# CAN_3V3.net
KiCad netlist of a schematic drawn in Altium Designer
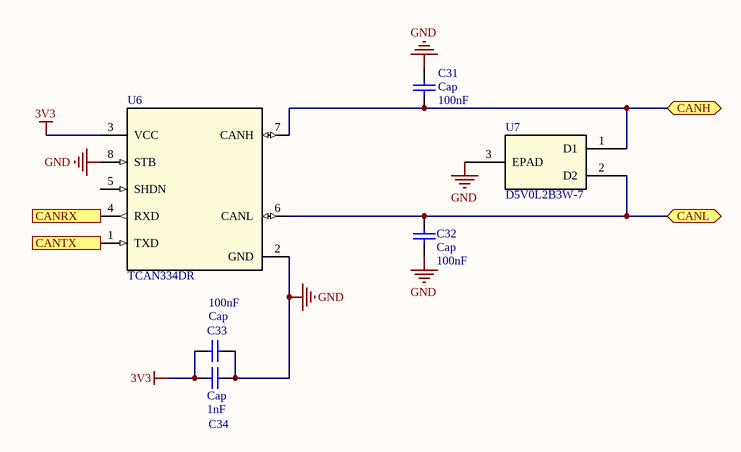
[diagram p0: CAN 3V3.SchDoc]

(export (version "E")
  (design (tool "Eeschema 10.0.6"))
  (components
    (comp (ref "C31")
      (value "Cap")
      (footprint "1608[0603]")
      (description "Capacitor")
      (fields (field (name "ALTIUM_VALUE") "100nF") (field (name "PUBLISHER") "Altium Limited"))
      (libsource (lib "Miscellaneous Devices") (part "Cap"))
    )
    (comp (ref "C32")
      (value "Cap")
      (footprint "1608[0603]")
      (description "Capacitor")
      (fields (field (name "ALTIUM_VALUE") "100nF") (field (name "PUBLISHER") "Altium Limited"))
      (libsource (lib "Miscellaneous Devices") (part "Cap"))
    )
    (comp (ref "C33")
      (value "Cap")
      (footprint "1608[0603]")
      (description "Capacitor")
      (fields (field (name "ALTIUM_VALUE") "100nF") (field (name "PUBLISHER") "Altium Limited"))
      (libsource (lib "Miscellaneous Devices") (part "Cap"))
    )
    (comp (ref "C34")
      (value "Cap")
      (footprint "1608[0603]")
      (description "Capacitor")
      (fields (field (name "ALTIUM_VALUE") "1nF") (field (name "PUBLISHER") "Altium Limited"))
      (libsource (lib "Miscellaneous Devices") (part "Cap"))
    )
    (comp (ref "U6")
      (value "TCAN334DR")
      (footprint "D0008A_N")
      (description "No Description Available")
      (fields
        (field (name "MANUFACTURER") "Texas Instruments")
        (field (name "COPYRIGHT") "Copyright (C) 2018 Accelerated Designs. All rights reserved")
      )
      (libsource (lib "CANTRAN3V3") (part "TCAN334DR"))
    )
    (comp (ref "U7")
      (value "D5V0L2B3W-7")
      (footprint "SOT-323_DIO")
      (description "No Description Available")
      (fields (field (name "COPYRIGHT") "Copyright (C) 2018 Accelerated Designs. All rights reserved"))
      (libsource (lib "D5V0L2B3W-7 library") (part "D5V0L2B3W-7"))
    )
  )
  (nets
    (net (code "1") (name "/CANH") (class "Default")
      (node (ref "C31") (pin "2") (pinfunction "2_2") (pintype "passive"))
      (node (ref "U6") (pin "7") (pinfunction "CANH_7") (pintype "bidirectional"))
      (node (ref "U7") (pin "1") (pinfunction "D1_1") (pintype "passive"))
    )
    (net (code "2") (name "/CANL") (class "Default")
      (node (ref "C32") (pin "2") (pinfunction "2_2") (pintype "passive"))
      (node (ref "U6") (pin "6") (pinfunction "CANL_6") (pintype "bidirectional"))
      (node (ref "U7") (pin "2") (pinfunction "D2_2") (pintype "passive"))
    )
    (net (code "3") (name "/CANRX") (class "Default")
      (node (ref "U6") (pin "4") (pinfunction "RXD_4") (pintype "output"))
    )
    (net (code "4") (name "/CANTX") (class "Default")
      (node (ref "U6") (pin "1") (pinfunction "TXD_1") (pintype "input"))
    )
    (net (code "5") (name "3V3") (class "Default")
      (node (ref "C33") (pin "1") (pinfunction "1_1") (pintype "passive"))
      (node (ref "C34") (pin "2") (pinfunction "2_2") (pintype "passive"))
      (node (ref "U6") (pin "3") (pinfunction "VCC_3") (pintype "power_in"))
    )
    (net (code "6") (name "GND") (class "Default")
      (node (ref "C31") (pin "1") (pinfunction "1_1") (pintype "passive"))
      (node (ref "C32") (pin "1") (pinfunction "1_1") (pintype "passive"))
      (node (ref "C33") (pin "2") (pinfunction "2_2") (pintype "passive"))
      (node (ref "C34") (pin "1") (pinfunction "1_1") (pintype "passive"))
      (node (ref "U6") (pin "2") (pinfunction "GND_2") (pintype "power_in"))
      (node (ref "U6") (pin "8") (pinfunction "STB_8") (pintype "input"))
      (node (ref "U7") (pin "3") (pinfunction "EPAD_3") (pintype "passive"))
    )
    (net (code "7") (name "unconnected-(U6-SHDN-Pad5)") (class "Default")
      (node (ref "U6") (pin "5") (pinfunction "SHDN_5") (pintype "input"))
    )
  )
)
